# Small_LED_Cube.net
KiCad netlist of a schematic drawn in EAGLE
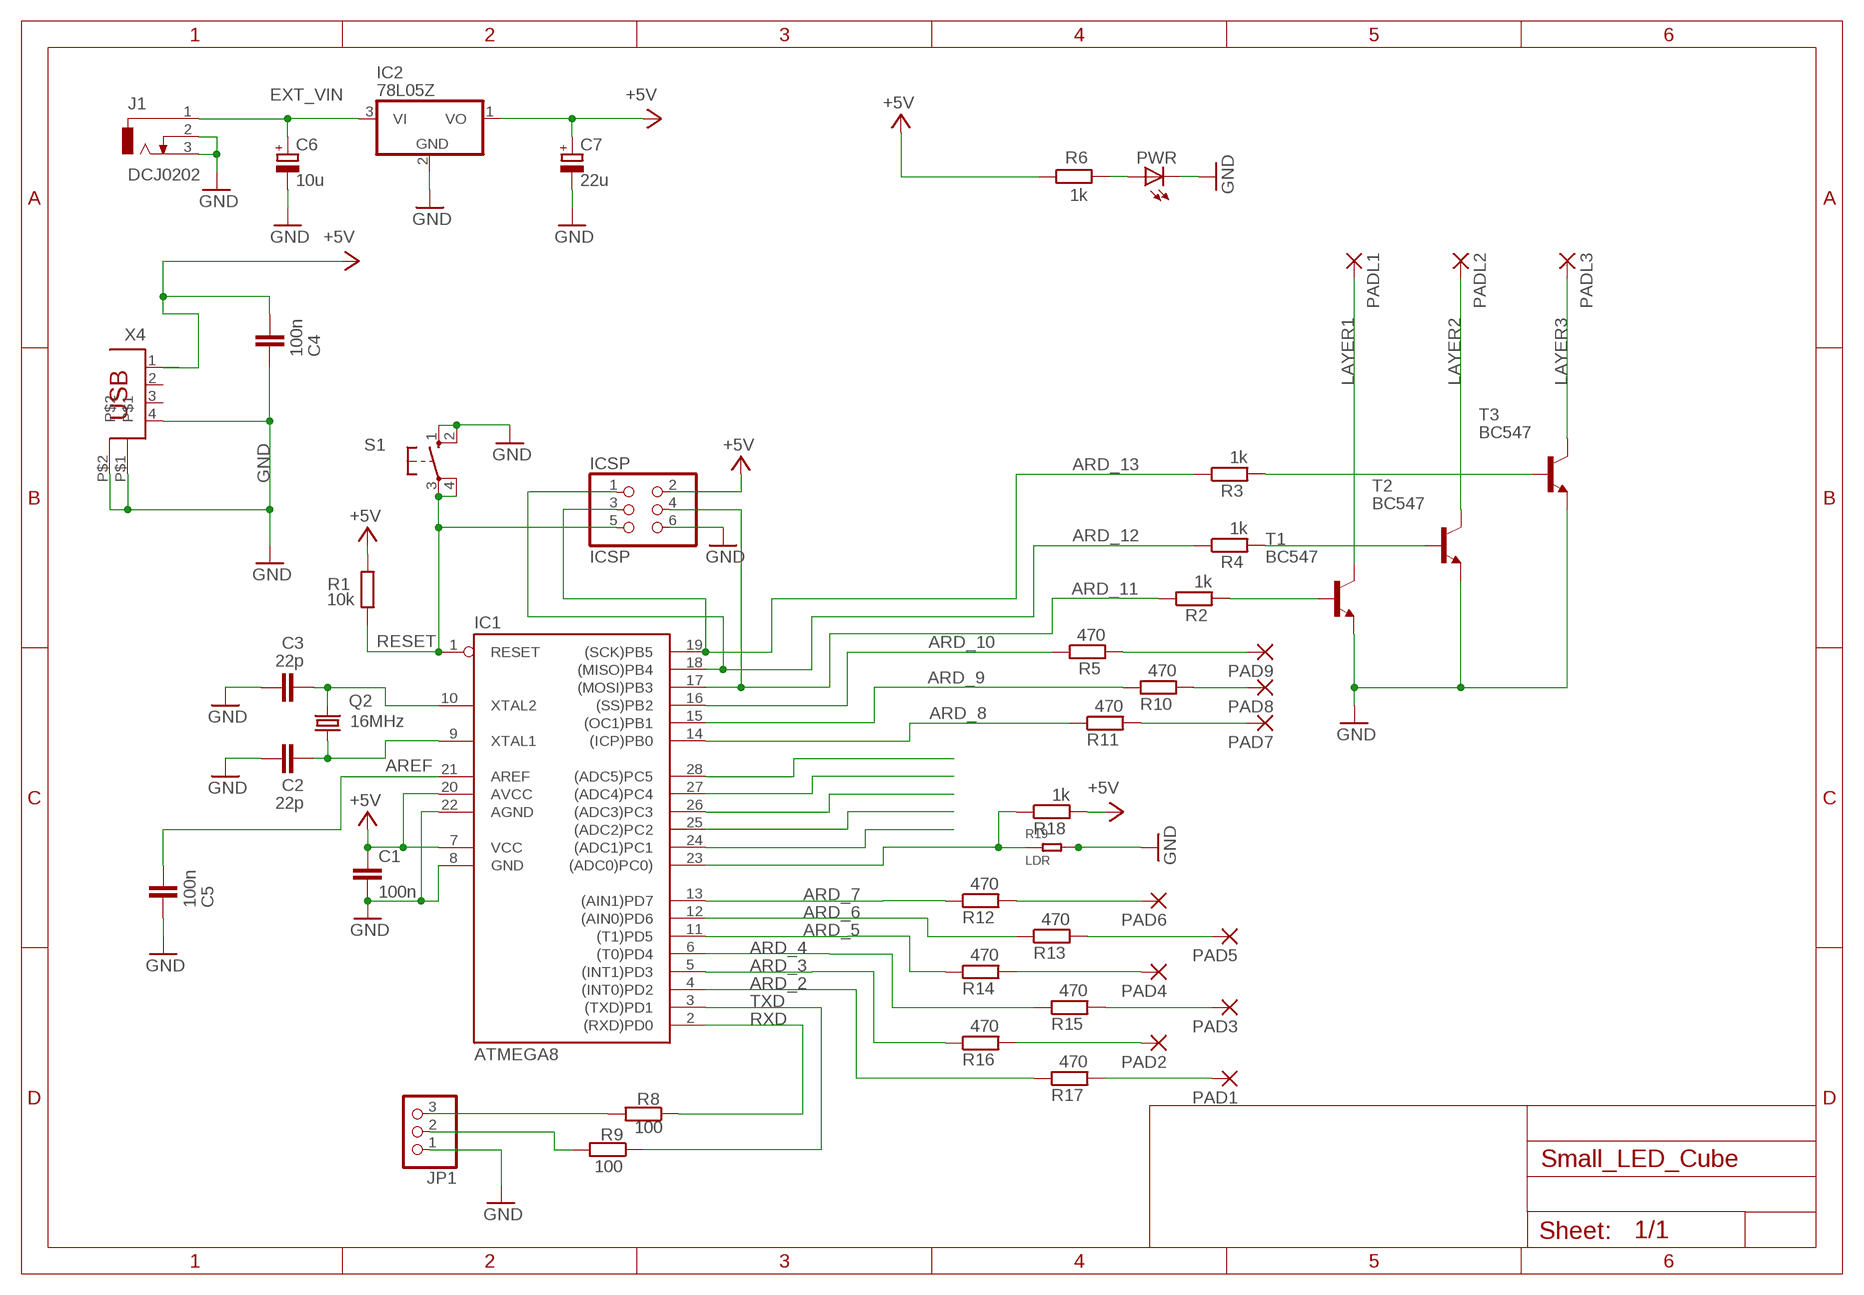
[diagram p0: schematic, sheet 1]

(export (version "E")
  (design (tool "Eeschema 10.0.6"))
  (components
    (comp (ref "C1")
      (value "100n")
      (footprint "eagle-import:C050-025X075")
      (libsource (lib "eagle-import") (part "C-EU050-025X075"))
    )
    (comp (ref "C2")
      (value "22p")
      (footprint "eagle-import:C025-024X044")
      (libsource (lib "eagle-import") (part "C-EU025-024X044"))
    )
    (comp (ref "C3")
      (value "22p")
      (footprint "eagle-import:C025-024X044")
      (libsource (lib "eagle-import") (part "C-EU025-024X044"))
    )
    (comp (ref "C4")
      (value "100n")
      (footprint "eagle-import:C050-025X075")
      (libsource (lib "eagle-import") (part "C-EU050-025X075"))
    )
    (comp (ref "C5")
      (value "100n")
      (footprint "eagle-import:C050-025X075")
      (libsource (lib "eagle-import") (part "C-EU050-025X075"))
    )
    (comp (ref "C6")
      (value "10u")
      (footprint "eagle-import:E2,5-5")
      (libsource (lib "eagle-import") (part "CPOL-EUE2.5-5"))
    )
    (comp (ref "C7")
      (value "22u")
      (footprint "eagle-import:E2,5-5")
      (libsource (lib "eagle-import") (part "CPOL-EUE2.5-5"))
    )
    (comp (ref "IC1")
      (value "ATMEGA8")
      (footprint "eagle-import:DIL28-3")
      (libsource (lib "eagle-import") (part "AT90S4433P"))
    )
    (comp (ref "IC2")
      (value "78L05Z")
      (footprint "eagle-import:TO92")
      (libsource (lib "eagle-import") (part "78ZL05"))
    )
    (comp (ref "ICSP")
      (value "ICSP")
      (footprint "eagle-import:2X03")
      (libsource (lib "eagle-import") (part "PINHD-2X3"))
    )
    (comp (ref "J1")
      (value "DCJ0202")
      (footprint "eagle-import:DCJ0202")
      (libsource (lib "eagle-import") (part "DCJ0202"))
    )
    (comp (ref "JP1")
      (value "PINHD-1X3")
      (footprint "eagle-import:1X03")
      (libsource (lib "eagle-import") (part "PINHD-1X3"))
    )
    (comp (ref "PAD1")
      (value "1,6/0,9")
      (footprint "eagle-import:1,6_0,9")
      (libsource (lib "eagle-import") (part "1,6/0,9"))
    )
    (comp (ref "PAD2")
      (value "1,6/0,9")
      (footprint "eagle-import:1,6_0,9")
      (libsource (lib "eagle-import") (part "1,6/0,9"))
    )
    (comp (ref "PAD3")
      (value "1,6/0,9")
      (footprint "eagle-import:1,6_0,9")
      (libsource (lib "eagle-import") (part "1,6/0,9"))
    )
    (comp (ref "PAD4")
      (value "1,6/0,9")
      (footprint "eagle-import:1,6_0,9")
      (libsource (lib "eagle-import") (part "1,6/0,9"))
    )
    (comp (ref "PAD5")
      (value "1,6/0,9")
      (footprint "eagle-import:1,6_0,9")
      (libsource (lib "eagle-import") (part "1,6/0,9"))
    )
    (comp (ref "PAD6")
      (value "1,6/0,9")
      (footprint "eagle-import:1,6_0,9")
      (libsource (lib "eagle-import") (part "1,6/0,9"))
    )
    (comp (ref "PAD7")
      (value "1,6/0,9")
      (footprint "eagle-import:1,6_0,9")
      (libsource (lib "eagle-import") (part "1,6/0,9"))
    )
    (comp (ref "PAD8")
      (value "1,6/0,9")
      (footprint "eagle-import:1,6_0,9")
      (libsource (lib "eagle-import") (part "1,6/0,9"))
    )
    (comp (ref "PAD9")
      (value "1,6/0,9")
      (footprint "eagle-import:1,6_0,9")
      (libsource (lib "eagle-import") (part "1,6/0,9"))
    )
    (comp (ref "PADL1")
      (value "1,6/0,9")
      (footprint "eagle-import:1,6_0,9")
      (libsource (lib "eagle-import") (part "1,6/0,9"))
    )
    (comp (ref "PADL2")
      (value "1,6/0,9")
      (footprint "eagle-import:1,6_0,9")
      (libsource (lib "eagle-import") (part "1,6/0,9"))
    )
    (comp (ref "PADL3")
      (value "1,6/0,9")
      (footprint "eagle-import:1,6_0,9")
      (libsource (lib "eagle-import") (part "1,6/0,9"))
    )
    (comp (ref "PWR")
      (value "LED3MM")
      (footprint "eagle-import:LED3MM")
      (libsource (lib "eagle-import") (part "LED3MM"))
    )
    (comp (ref "Q2")
      (value "16MHz")
      (footprint "eagle-import:HC49_S")
      (libsource (lib "eagle-import") (part "CRYTALHC49S"))
    )
    (comp (ref "R1")
      (value "10k")
      (footprint "eagle-import:0204_7@1")
      (libsource (lib "eagle-import") (part "R-EU_0204/7"))
    )
    (comp (ref "R2")
      (value "1k")
      (footprint "eagle-import:0204_7@1")
      (libsource (lib "eagle-import") (part "R-EU_0204/7"))
    )
    (comp (ref "R3")
      (value "1k")
      (footprint "eagle-import:0204_7@1")
      (libsource (lib "eagle-import") (part "R-EU_0204/7"))
    )
    (comp (ref "R4")
      (value "1k")
      (footprint "eagle-import:0204_7@1")
      (libsource (lib "eagle-import") (part "R-EU_0204/7"))
    )
    (comp (ref "R5")
      (value "470")
      (footprint "eagle-import:0204_7@1")
      (libsource (lib "eagle-import") (part "R-EU_0204/7"))
    )
    (comp (ref "R6")
      (value "1k")
      (footprint "eagle-import:0204_7@1")
      (libsource (lib "eagle-import") (part "R-EU_0204/7"))
    )
    (comp (ref "R8")
      (value "100")
      (footprint "eagle-import:0204_7@1")
      (libsource (lib "eagle-import") (part "R-EU_0204/7"))
    )
    (comp (ref "R9")
      (value "100")
      (footprint "eagle-import:0204_7@1")
      (libsource (lib "eagle-import") (part "R-EU_0204/7"))
    )
    (comp (ref "R10")
      (value "470")
      (footprint "eagle-import:0204_7@1")
      (libsource (lib "eagle-import") (part "R-EU_0204/7"))
    )
    (comp (ref "R11")
      (value "470")
      (footprint "eagle-import:0204_7@1")
      (libsource (lib "eagle-import") (part "R-EU_0204/7"))
    )
    (comp (ref "R12")
      (value "470")
      (footprint "eagle-import:0204_7@1")
      (libsource (lib "eagle-import") (part "R-EU_0204/7"))
    )
    (comp (ref "R13")
      (value "470")
      (footprint "eagle-import:0204_7@1")
      (libsource (lib "eagle-import") (part "R-EU_0204/7"))
    )
    (comp (ref "R14")
      (value "470")
      (footprint "eagle-import:0204_7@1")
      (libsource (lib "eagle-import") (part "R-EU_0204/7"))
    )
    (comp (ref "R15")
      (value "470")
      (footprint "eagle-import:0204_7@1")
      (libsource (lib "eagle-import") (part "R-EU_0204/7"))
    )
    (comp (ref "R16")
      (value "470")
      (footprint "eagle-import:0204_7@1")
      (libsource (lib "eagle-import") (part "R-EU_0204/7"))
    )
    (comp (ref "R17")
      (value "470")
      (footprint "eagle-import:0204_7@1")
      (libsource (lib "eagle-import") (part "R-EU_0204/7"))
    )
    (comp (ref "R18")
      (value "1k")
      (footprint "eagle-import:0204_7@1")
      (libsource (lib "eagle-import") (part "R-EU_0204/7"))
    )
    (comp (ref "R19")
      (value "LDR")
      (footprint "eagle-import:PR-2.8-4.2X4.9MM")
      (fields (field (name "MPN") "LDR-VT90N2"))
      (libsource (lib "eagle-import") (part "DIP-RES-LDR(2P-D2.3X3.7MM)"))
    )
    (comp (ref "S1")
      (value "10-XX")
      (footprint "eagle-import:B3F-10XX")
      (libsource (lib "eagle-import") (part "10-XX"))
    )
    (comp (ref "T1")
      (value "BC547")
      (footprint "eagle-import:TO92")
      (libsource (lib "eagle-import") (part "BC547"))
    )
    (comp (ref "T2")
      (value "BC547")
      (footprint "eagle-import:TO92")
      (libsource (lib "eagle-import") (part "BC547"))
    )
    (comp (ref "T3")
      (value "BC547")
      (footprint "eagle-import:TO92")
      (libsource (lib "eagle-import") (part "BC547"))
    )
    (comp (ref "X4")
      (value "PN61729")
      (footprint "eagle-import:PN61729")
      (libsource (lib "eagle-import") (part "PN61729"))
    )
  )
  (nets
    (net (code "1") (name "+5V") (class "Default")
      (node (ref "C1") (pin "1") (pinfunction "1_1") (pintype "passive"))
      (node (ref "C4") (pin "1") (pinfunction "1_1") (pintype "passive"))
      (node (ref "C7") (pin "+") (pinfunction "+_+") (pintype "passive"))
      (node (ref "IC1") (pin "20") (pinfunction "AVCC_20") (pintype "power_in"))
      (node (ref "IC1") (pin "7") (pinfunction "VCC_7") (pintype "power_in"))
      (node (ref "IC2") (pin "1") (pinfunction "VO_1") (pintype "passive"))
      (node (ref "ICSP") (pin "2") (pinfunction "2_2") (pintype "passive"))
      (node (ref "R1") (pin "2") (pinfunction "2_2") (pintype "passive"))
      (node (ref "R18") (pin "2") (pinfunction "2_2") (pintype "passive"))
      (node (ref "R6") (pin "1") (pinfunction "1_1") (pintype "passive"))
      (node (ref "X4") (pin "1") (pinfunction "1_1") (pintype "bidirectional"))
    )
    (net (code "2") (name "/ARD_2") (class "Default")
      (node (ref "IC1") (pin "4") (pinfunction "(INT0)PD2_4") (pintype "bidirectional"))
      (node (ref "R17") (pin "1") (pinfunction "1_1") (pintype "passive"))
    )
    (net (code "3") (name "/ARD_3") (class "Default")
      (node (ref "IC1") (pin "5") (pinfunction "(INT1)PD3_5") (pintype "bidirectional"))
      (node (ref "R16") (pin "1") (pinfunction "1_1") (pintype "passive"))
    )
    (net (code "4") (name "/ARD_4") (class "Default")
      (node (ref "IC1") (pin "6") (pinfunction "(T0)PD4_6") (pintype "bidirectional"))
      (node (ref "R15") (pin "1") (pinfunction "1_1") (pintype "passive"))
    )
    (net (code "5") (name "/ARD_5") (class "Default")
      (node (ref "IC1") (pin "11") (pinfunction "(T1)PD5_11") (pintype "bidirectional"))
      (node (ref "R14") (pin "1") (pinfunction "1_1") (pintype "passive"))
    )
    (net (code "6") (name "/ARD_6") (class "Default")
      (node (ref "IC1") (pin "12") (pinfunction "(AIN0)PD6_12") (pintype "bidirectional"))
      (node (ref "R13") (pin "1") (pinfunction "1_1") (pintype "passive"))
    )
    (net (code "7") (name "/ARD_7") (class "Default")
      (node (ref "IC1") (pin "13") (pinfunction "(AIN1)PD7_13") (pintype "bidirectional"))
      (node (ref "R12") (pin "1") (pinfunction "1_1") (pintype "passive"))
    )
    (net (code "8") (name "/ARD_8") (class "Default")
      (node (ref "IC1") (pin "14") (pinfunction "(ICP)PB0_14") (pintype "bidirectional"))
      (node (ref "R11") (pin "1") (pinfunction "1_1") (pintype "passive"))
    )
    (net (code "9") (name "/ARD_9") (class "Default")
      (node (ref "IC1") (pin "15") (pinfunction "(OC1)PB1_15") (pintype "bidirectional"))
      (node (ref "R10") (pin "1") (pinfunction "1_1") (pintype "passive"))
    )
    (net (code "10") (name "/ARD_10") (class "Default")
      (node (ref "IC1") (pin "16") (pinfunction "(SS)PB2_16") (pintype "bidirectional"))
      (node (ref "R5") (pin "1") (pinfunction "1_1") (pintype "passive"))
    )
    (net (code "11") (name "/ARD_11") (class "Default")
      (node (ref "IC1") (pin "17") (pinfunction "(MOSI)PB3_17") (pintype "bidirectional"))
      (node (ref "ICSP") (pin "4") (pinfunction "4_4") (pintype "passive"))
      (node (ref "R2") (pin "1") (pinfunction "1_1") (pintype "passive"))
    )
    (net (code "12") (name "/ARD_12") (class "Default")
      (node (ref "IC1") (pin "18") (pinfunction "(MISO)PB4_18") (pintype "bidirectional"))
      (node (ref "ICSP") (pin "1") (pinfunction "1_1") (pintype "passive"))
      (node (ref "R4") (pin "1") (pinfunction "1_1") (pintype "passive"))
    )
    (net (code "13") (name "/ARD_13") (class "Default")
      (node (ref "IC1") (pin "19") (pinfunction "(SCK)PB5_19") (pintype "bidirectional"))
      (node (ref "ICSP") (pin "3") (pinfunction "3_3") (pintype "passive"))
      (node (ref "R3") (pin "1") (pinfunction "1_1") (pintype "passive"))
    )
    (net (code "14") (name "/AREF") (class "Default")
      (node (ref "C5") (pin "1") (pinfunction "1_1") (pintype "passive"))
      (node (ref "IC1") (pin "21") (pinfunction "AREF_21") (pintype "power_in"))
    )
    (net (code "15") (name "/EXT_VIN") (class "Default")
      (node (ref "C6") (pin "+") (pinfunction "+_+") (pintype "passive"))
      (node (ref "IC2") (pin "3") (pinfunction "VI_3") (pintype "input"))
      (node (ref "J1") (pin "1") (pinfunction "1_1") (pintype "passive"))
    )
    (net (code "16") (name "/LAYER1") (class "Default")
      (node (ref "PADL1") (pin "1") (pinfunction "P_1") (pintype "passive"))
      (node (ref "T1") (pin "3") (pinfunction "C_3") (pintype "passive"))
    )
    (net (code "17") (name "/LAYER2") (class "Default")
      (node (ref "PADL2") (pin "1") (pinfunction "P_1") (pintype "passive"))
      (node (ref "T2") (pin "3") (pinfunction "C_3") (pintype "passive"))
    )
    (net (code "18") (name "/LAYER3") (class "Default")
      (node (ref "PADL3") (pin "1") (pinfunction "P_1") (pintype "passive"))
      (node (ref "T3") (pin "3") (pinfunction "C_3") (pintype "passive"))
    )
    (net (code "19") (name "/RESET") (class "Default")
      (node (ref "IC1") (pin "1") (pinfunction "RESET_1") (pintype "input"))
      (node (ref "ICSP") (pin "5") (pinfunction "5_5") (pintype "passive"))
      (node (ref "R1") (pin "1") (pinfunction "1_1") (pintype "passive"))
      (node (ref "S1") (pin "3") (pinfunction "P_3") (pintype "passive"))
      (node (ref "S1") (pin "4") (pinfunction "P1_4") (pintype "passive"))
    )
    (net (code "20") (name "/RXD") (class "Default")
      (node (ref "IC1") (pin "2") (pinfunction "(RXD)PD0_2") (pintype "bidirectional"))
      (node (ref "R8") (pin "1") (pinfunction "1_1") (pintype "passive"))
    )
    (net (code "21") (name "/TXD") (class "Default")
      (node (ref "IC1") (pin "3") (pinfunction "(TXD)PD1_3") (pintype "bidirectional"))
      (node (ref "R9") (pin "1") (pinfunction "1_1") (pintype "passive"))
    )
    (net (code "22") (name "GND") (class "Default")
      (node (ref "C1") (pin "2") (pinfunction "2_2") (pintype "passive"))
      (node (ref "C2") (pin "1") (pinfunction "1_1") (pintype "passive"))
      (node (ref "C3") (pin "1") (pinfunction "1_1") (pintype "passive"))
      (node (ref "C4") (pin "2") (pinfunction "2_2") (pintype "passive"))
      (node (ref "C5") (pin "2") (pinfunction "2_2") (pintype "passive"))
      (node (ref "C6") (pin "-") (pinfunction "-_-") (pintype "passive"))
      (node (ref "C7") (pin "-") (pinfunction "-_-") (pintype "passive"))
      (node (ref "IC1") (pin "22") (pinfunction "AGND_22") (pintype "power_in"))
      (node (ref "IC1") (pin "8") (pinfunction "GND_8") (pintype "power_in"))
      (node (ref "IC2") (pin "2") (pinfunction "GND_2") (pintype "passive"))
      (node (ref "ICSP") (pin "6") (pinfunction "6_6") (pintype "passive"))
      (node (ref "J1") (pin "2") (pinfunction "2_2") (pintype "passive"))
      (node (ref "J1") (pin "3") (pinfunction "3_3") (pintype "passive"))
      (node (ref "JP1") (pin "1") (pinfunction "1_1") (pintype "passive"))
      (node (ref "PWR") (pin "K") (pinfunction "C_K") (pintype "passive"))
      (node (ref "R19") (pin "2") (pinfunction "2_2") (pintype "passive"))
      (node (ref "S1") (pin "1") (pinfunction "S_1") (pintype "passive"))
      (node (ref "S1") (pin "2") (pinfunction "S1_2") (pintype "passive"))
      (node (ref "T1") (pin "1") (pinfunction "E_1") (pintype "passive"))
      (node (ref "T2") (pin "1") (pinfunction "E_1") (pintype "passive"))
      (node (ref "T3") (pin "1") (pinfunction "E_1") (pintype "passive"))
      (node (ref "X4") (pin "4") (pinfunction "4_4") (pintype "bidirectional"))
      (node (ref "X4") (pin "P$1") (pinfunction "P$1_P$1") (pintype "bidirectional"))
      (node (ref "X4") (pin "P$2") (pinfunction "P$2_P$2") (pintype "bidirectional"))
    )
    (net (code "23") (name "Net-(IC1-(ADC0)PC0))") (class "Default")
      (node (ref "IC1") (pin "23") (pinfunction "(ADC0)PC0)_23") (pintype "bidirectional"))
      (node (ref "R18") (pin "1") (pinfunction "1_1") (pintype "passive"))
      (node (ref "R19") (pin "1") (pinfunction "1_1") (pintype "passive"))
    )
    (net (code "24") (name "Net-(IC1-XTAL1)") (class "Default")
      (node (ref "C2") (pin "2") (pinfunction "2_2") (pintype "passive"))
      (node (ref "IC1") (pin "9") (pinfunction "XTAL1_9") (pintype "bidirectional"))
      (node (ref "Q2") (pin "1") (pinfunction "1_1") (pintype "passive"))
    )
    (net (code "25") (name "Net-(IC1-XTAL2)") (class "Default")
      (node (ref "C3") (pin "2") (pinfunction "2_2") (pintype "passive"))
      (node (ref "IC1") (pin "10") (pinfunction "XTAL2_10") (pintype "bidirectional"))
      (node (ref "Q2") (pin "2") (pinfunction "2_2") (pintype "passive"))
    )
    (net (code "26") (name "Net-(JP1-Pad2)") (class "Default")
      (node (ref "JP1") (pin "2") (pinfunction "2_2") (pintype "passive"))
      (node (ref "R9") (pin "2") (pinfunction "2_2") (pintype "passive"))
    )
    (net (code "27") (name "Net-(JP1-Pad3)") (class "Default")
      (node (ref "JP1") (pin "3") (pinfunction "3_3") (pintype "passive"))
      (node (ref "R8") (pin "2") (pinfunction "2_2") (pintype "passive"))
    )
    (net (code "28") (name "Net-(PAD1-P)") (class "Default")
      (node (ref "PAD1") (pin "1") (pinfunction "P_1") (pintype "passive"))
      (node (ref "R17") (pin "2") (pinfunction "2_2") (pintype "passive"))
    )
    (net (code "29") (name "Net-(PAD2-P)") (class "Default")
      (node (ref "PAD2") (pin "1") (pinfunction "P_1") (pintype "passive"))
      (node (ref "R16") (pin "2") (pinfunction "2_2") (pintype "passive"))
    )
    (net (code "30") (name "Net-(PAD3-P)") (class "Default")
      (node (ref "PAD3") (pin "1") (pinfunction "P_1") (pintype "passive"))
      (node (ref "R15") (pin "2") (pinfunction "2_2") (pintype "passive"))
    )
    (net (code "31") (name "Net-(PAD4-P)") (class "Default")
      (node (ref "PAD4") (pin "1") (pinfunction "P_1") (pintype "passive"))
      (node (ref "R14") (pin "2") (pinfunction "2_2") (pintype "passive"))
    )
    (net (code "32") (name "Net-(PAD5-P)") (class "Default")
      (node (ref "PAD5") (pin "1") (pinfunction "P_1") (pintype "passive"))
      (node (ref "R13") (pin "2") (pinfunction "2_2") (pintype "passive"))
    )
    (net (code "33") (name "Net-(PAD6-P)") (class "Default")
      (node (ref "PAD6") (pin "1") (pinfunction "P_1") (pintype "passive"))
      (node (ref "R12") (pin "2") (pinfunction "2_2") (pintype "passive"))
    )
    (net (code "34") (name "Net-(PAD7-P)") (class "Default")
      (node (ref "PAD7") (pin "1") (pinfunction "P_1") (pintype "passive"))
      (node (ref "R11") (pin "2") (pinfunction "2_2") (pintype "passive"))
    )
    (net (code "35") (name "Net-(PAD8-P)") (class "Default")
      (node (ref "PAD8") (pin "1") (pinfunction "P_1") (pintype "passive"))
      (node (ref "R10") (pin "2") (pinfunction "2_2") (pintype "passive"))
    )
    (net (code "36") (name "Net-(PAD9-P)") (class "Default")
      (node (ref "PAD9") (pin "1") (pinfunction "P_1") (pintype "passive"))
      (node (ref "R5") (pin "2") (pinfunction "2_2") (pintype "passive"))
    )
    (net (code "37") (name "Net-(PWR-PadA)") (class "Default")
      (node (ref "PWR") (pin "A") (pinfunction "A_A") (pintype "passive"))
      (node (ref "R6") (pin "2") (pinfunction "2_2") (pintype "passive"))
    )
    (net (code "38") (name "Net-(T1-B)") (class "Default")
      (node (ref "R2") (pin "2") (pinfunction "2_2") (pintype "passive"))
      (node (ref "T1") (pin "2") (pinfunction "B_2") (pintype "passive"))
    )
    (net (code "39") (name "Net-(T2-B)") (class "Default")
      (node (ref "R4") (pin "2") (pinfunction "2_2") (pintype "passive"))
      (node (ref "T2") (pin "2") (pinfunction "B_2") (pintype "passive"))
    )
    (net (code "40") (name "Net-(T3-B)") (class "Default")
      (node (ref "R3") (pin "2") (pinfunction "2_2") (pintype "passive"))
      (node (ref "T3") (pin "2") (pinfunction "B_2") (pintype "passive"))
    )
    (net (code "41") (name "unconnected-(IC1-(ADC1)PC1-Pad24)") (class "Default")
      (node (ref "IC1") (pin "24") (pinfunction "(ADC1)PC1_24") (pintype "bidirectional"))
    )
    (net (code "42") (name "unconnected-(IC1-(ADC2)PC2-Pad25)") (class "Default")
      (node (ref "IC1") (pin "25") (pinfunction "(ADC2)PC2_25") (pintype "bidirectional"))
    )
    (net (code "43") (name "unconnected-(IC1-(ADC3)PC3-Pad26)") (class "Default")
      (node (ref "IC1") (pin "26") (pinfunction "(ADC3)PC3_26") (pintype "bidirectional"))
    )
    (net (code "44") (name "unconnected-(IC1-(ADC4)PC4-Pad27)") (class "Default")
      (node (ref "IC1") (pin "27") (pinfunction "(ADC4)PC4_27") (pintype "bidirectional"))
    )
    (net (code "45") (name "unconnected-(IC1-(ADC5)PC5-Pad28)") (class "Default")
      (node (ref "IC1") (pin "28") (pinfunction "(ADC5)PC5_28") (pintype "bidirectional"))
    )
    (net (code "46") (name "unconnected-(X4-Pad2)") (class "Default")
      (node (ref "X4") (pin "2") (pinfunction "2_2") (pintype "bidirectional"))
    )
    (net (code "47") (name "unconnected-(X4-Pad3)") (class "Default")
      (node (ref "X4") (pin "3") (pinfunction "3_3") (pintype "bidirectional"))
    )
  )
)
